# DPUNK-Schematic.net
KiCad netlist of a schematic drawn in EasyEDA
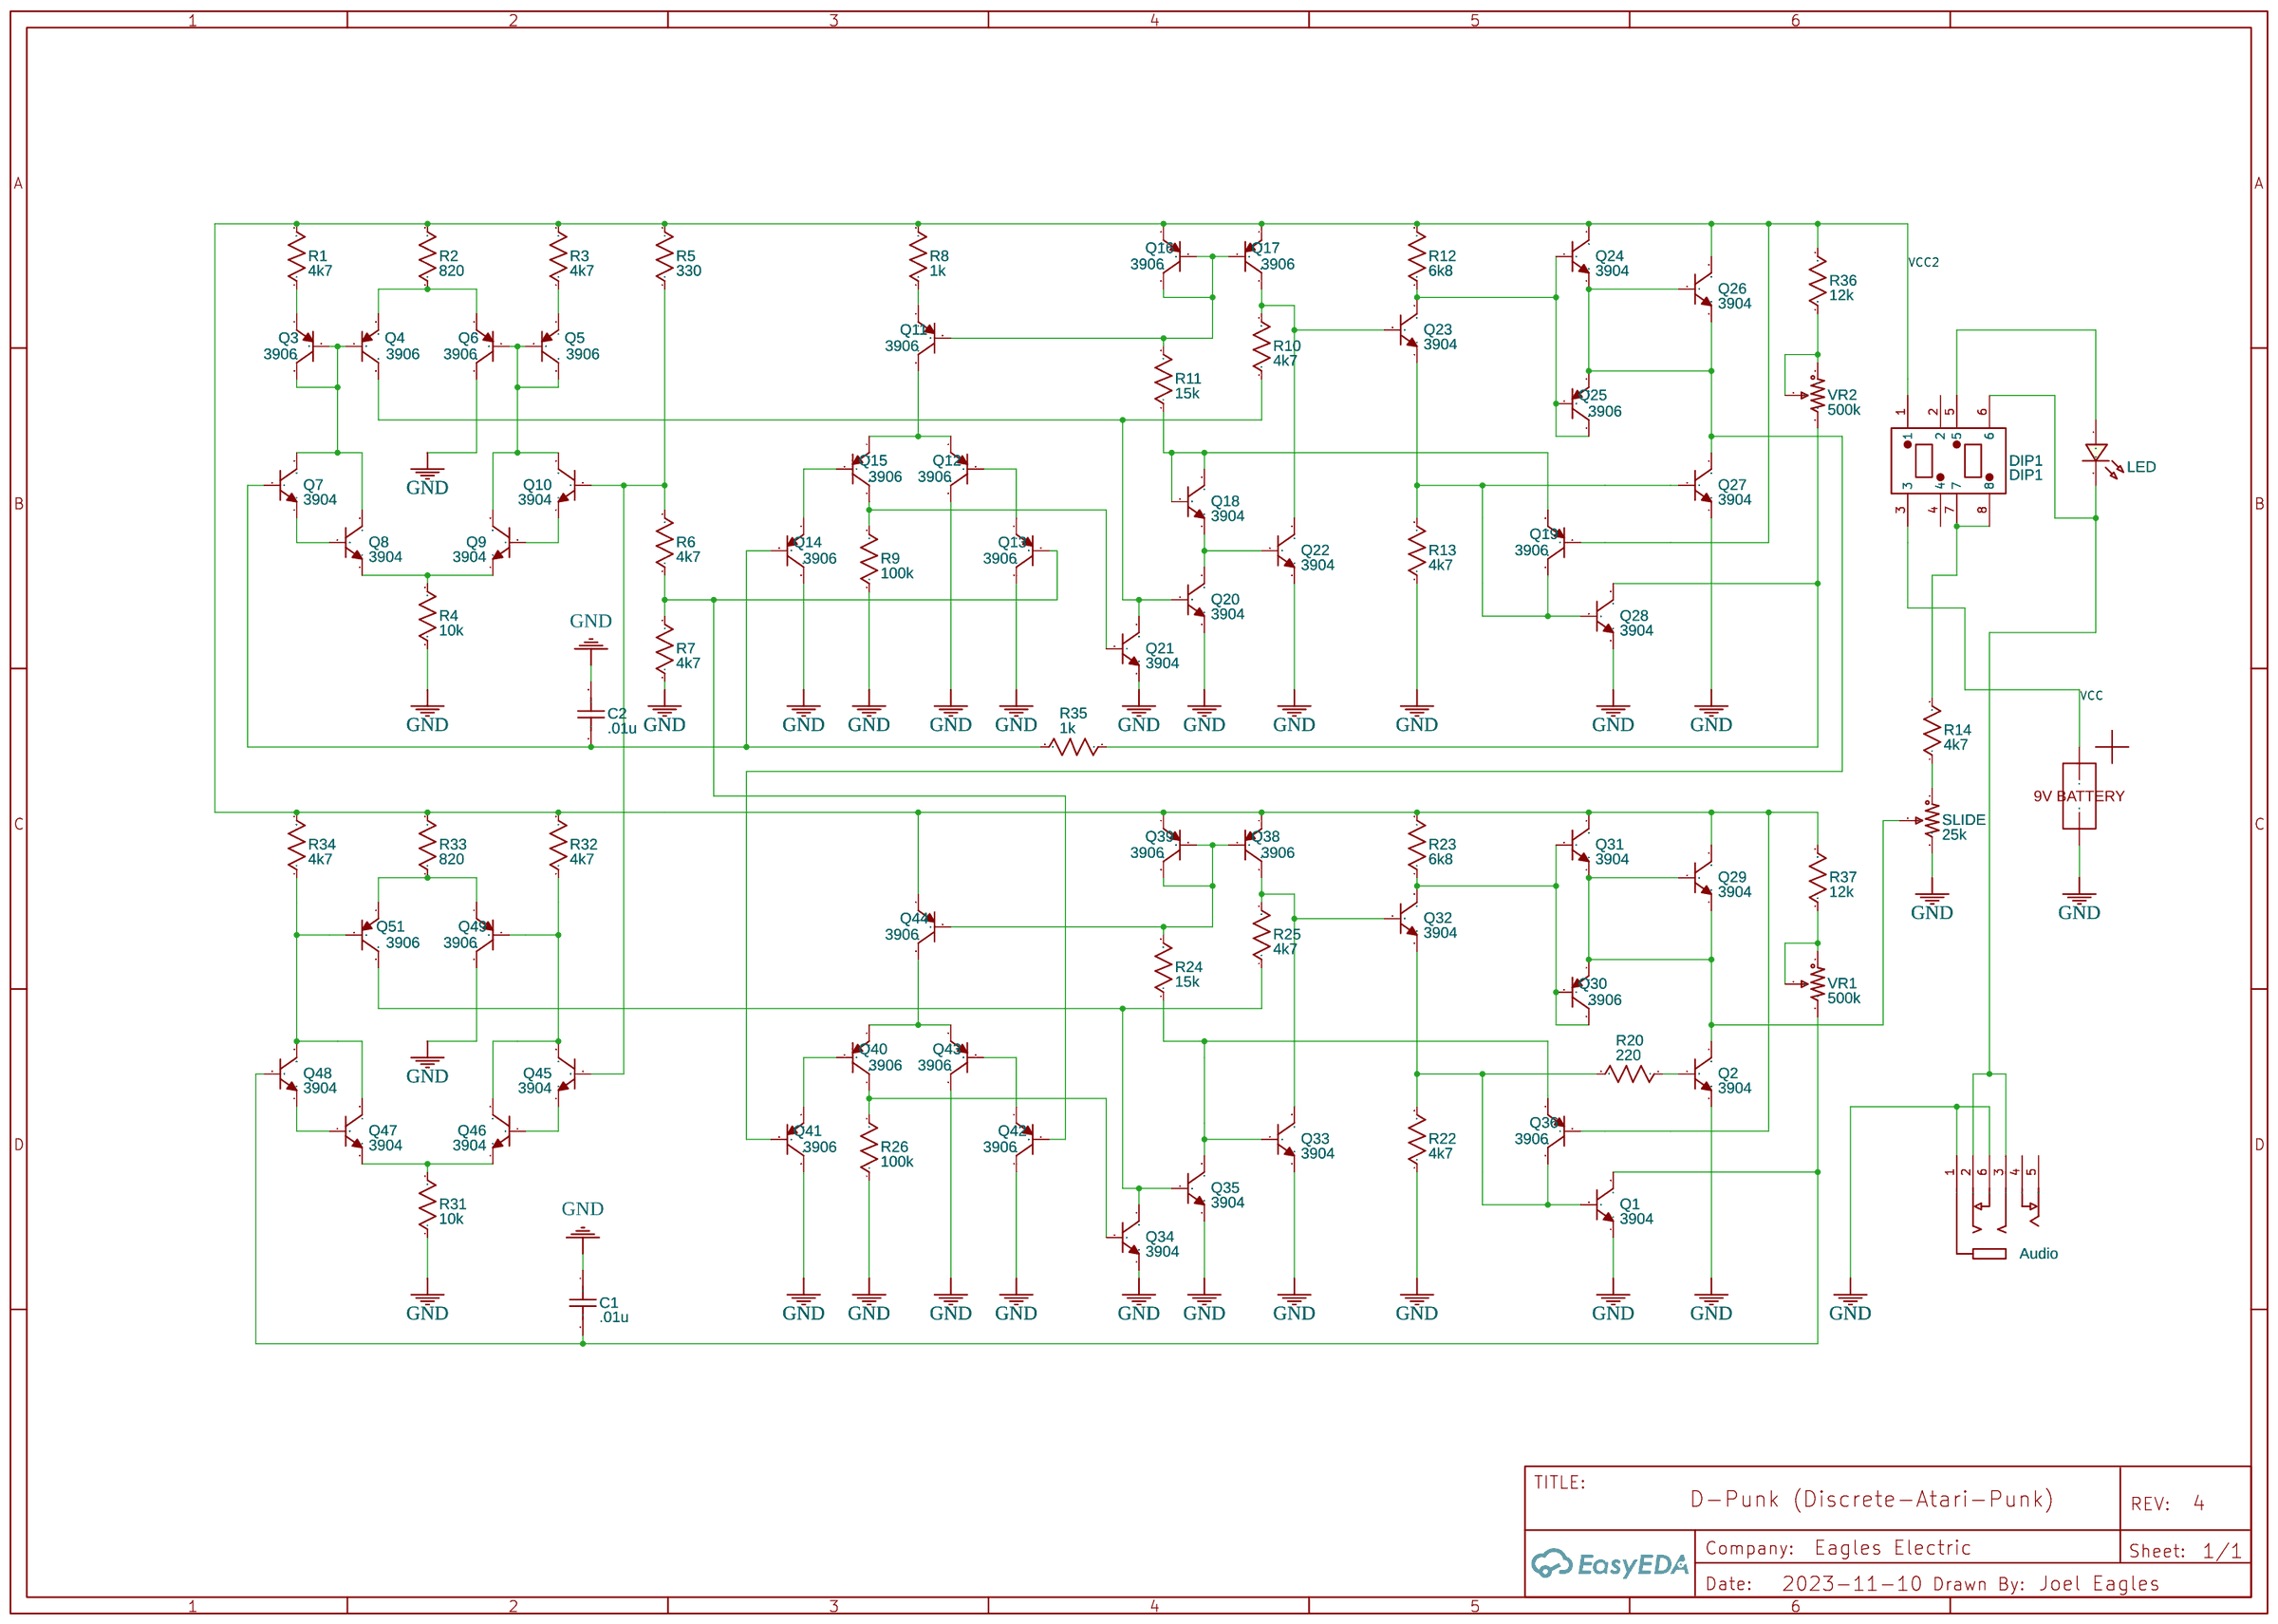
[diagram p0: schematic sheet]

(export (version "E")
  (design (tool "Eeschema 10.0.6"))
  (components
    (comp (ref "9V") (value "9v battery connector") (libsource (lib "") (part "9v battery connector")))
    (comp (ref "AUX")
      (value "Audio")
      (fields (field (name "Manufacturer") "ADAM TECH"))
      (libsource (lib "") (part "ASJ-99H-R-HT-T/R"))
    )
    (comp (ref "C1") (value ".01u") (libsource (lib "") (part "C_0603_US")))
    (comp (ref "C2") (value ".01u") (libsource (lib "") (part "C_0603_US_1")))
    (comp (ref "DIP1")
      (value "DIP1")
      (fields (field (name "Manufacturer Part") "78J02T") (field (name "Manufacturer") "Grayhill"))
      (libsource (lib "") (part "78J02T"))
    )
    (comp (ref "LED")
      (value "LED")
      (fields
        (field (name "Manufacturer Part") "333-2SURD/S530-A3")
        (field (name "Manufacturer") "EVERLIGHT(台湾亿光)")
      )
      (libsource (lib "") (part "LED-TH-5mm_R"))
    )
    (comp (ref "Q1")
      (value "3904")
      (fields (field (name "Manufacturer Part") "2N3904") (field (name "Manufacturer") "SEMTECH"))
      (libsource (lib "") (part "2N3904(TO-92)"))
    )
    (comp (ref "Q2")
      (value "3904")
      (fields (field (name "Manufacturer Part") "2N3904") (field (name "Manufacturer") "SEMTECH"))
      (libsource (lib "") (part "2N3904(TO-92)"))
    )
    (comp (ref "Q3")
      (value "3906")
      (fields (field (name "Manufacturer Part") "2N3906") (field (name "Manufacturer") "CJ"))
      (libsource (lib "") (part "2N3906(TO-92)_1"))
    )
    (comp (ref "Q4")
      (value "3906")
      (fields (field (name "Manufacturer Part") "2N3906") (field (name "Manufacturer") "CJ"))
      (libsource (lib "") (part "2N3906(TO-92)"))
    )
    (comp (ref "Q5")
      (value "3906")
      (fields (field (name "Manufacturer Part") "2N3906") (field (name "Manufacturer") "CJ"))
      (libsource (lib "") (part "2N3906(TO-92)"))
    )
    (comp (ref "Q6")
      (value "3906")
      (fields (field (name "Manufacturer Part") "2N3906") (field (name "Manufacturer") "CJ"))
      (libsource (lib "") (part "2N3906(TO-92)_1"))
    )
    (comp (ref "Q7")
      (value "3904")
      (fields (field (name "Manufacturer Part") "2N3904") (field (name "Manufacturer") "SEMTECH"))
      (libsource (lib "") (part "2N3904(TO-92)"))
    )
    (comp (ref "Q8")
      (value "3904")
      (fields (field (name "Manufacturer Part") "2N3904") (field (name "Manufacturer") "SEMTECH"))
      (libsource (lib "") (part "2N3904(TO-92)"))
    )
    (comp (ref "Q9")
      (value "3904")
      (fields (field (name "Manufacturer Part") "2N3904") (field (name "Manufacturer") "SEMTECH"))
      (libsource (lib "") (part "2N3904(TO-92)_1"))
    )
    (comp (ref "Q10")
      (value "3904")
      (fields (field (name "Manufacturer Part") "2N3904") (field (name "Manufacturer") "SEMTECH"))
      (libsource (lib "") (part "2N3904(TO-92)_1"))
    )
    (comp (ref "Q11")
      (value "3906")
      (fields (field (name "Manufacturer Part") "2N3906") (field (name "Manufacturer") "CJ"))
      (libsource (lib "") (part "2N3906(TO-92)_1"))
    )
    (comp (ref "Q12")
      (value "3906")
      (fields (field (name "Manufacturer Part") "2N3906") (field (name "Manufacturer") "CJ"))
      (libsource (lib "") (part "2N3906(TO-92)_1"))
    )
    (comp (ref "Q13")
      (value "3906")
      (fields (field (name "Manufacturer Part") "2N3906") (field (name "Manufacturer") "CJ"))
      (libsource (lib "") (part "2N3906(TO-92)_1"))
    )
    (comp (ref "Q14")
      (value "3906")
      (fields (field (name "Manufacturer Part") "2N3906") (field (name "Manufacturer") "CJ"))
      (libsource (lib "") (part "2N3906(TO-92)"))
    )
    (comp (ref "Q15")
      (value "3906")
      (fields (field (name "Manufacturer Part") "2N3906") (field (name "Manufacturer") "CJ"))
      (libsource (lib "") (part "2N3906(TO-92)"))
    )
    (comp (ref "Q16")
      (value "3906")
      (fields (field (name "Manufacturer Part") "2N3906") (field (name "Manufacturer") "CJ"))
      (libsource (lib "") (part "2N3906(TO-92)_1"))
    )
    (comp (ref "Q17")
      (value "3906")
      (fields (field (name "Manufacturer Part") "2N3906") (field (name "Manufacturer") "CJ"))
      (libsource (lib "") (part "2N3906(TO-92)"))
    )
    (comp (ref "Q18")
      (value "3904")
      (fields (field (name "Manufacturer Part") "2N3904") (field (name "Manufacturer") "SEMTECH"))
      (libsource (lib "") (part "2N3904(TO-92)"))
    )
    (comp (ref "Q19")
      (value "3906")
      (fields (field (name "Manufacturer Part") "2N3906") (field (name "Manufacturer") "CJ"))
      (libsource (lib "") (part "2N3906(TO-92)_1"))
    )
    (comp (ref "Q20")
      (value "3904")
      (fields (field (name "Manufacturer Part") "2N3904") (field (name "Manufacturer") "SEMTECH"))
      (libsource (lib "") (part "2N3904(TO-92)"))
    )
    (comp (ref "Q21")
      (value "3904")
      (fields (field (name "Manufacturer Part") "2N3904") (field (name "Manufacturer") "SEMTECH"))
      (libsource (lib "") (part "2N3904(TO-92)"))
    )
    (comp (ref "Q22")
      (value "3904")
      (fields (field (name "Manufacturer Part") "2N3904") (field (name "Manufacturer") "SEMTECH"))
      (libsource (lib "") (part "2N3904(TO-92)"))
    )
    (comp (ref "Q23")
      (value "3904")
      (fields (field (name "Manufacturer Part") "2N3904") (field (name "Manufacturer") "SEMTECH"))
      (libsource (lib "") (part "2N3904(TO-92)"))
    )
    (comp (ref "Q24")
      (value "3904")
      (fields (field (name "Manufacturer Part") "2N3904") (field (name "Manufacturer") "SEMTECH"))
      (libsource (lib "") (part "2N3904(TO-92)"))
    )
    (comp (ref "Q25")
      (value "3906")
      (fields (field (name "Manufacturer Part") "2N3906") (field (name "Manufacturer") "CJ"))
      (libsource (lib "") (part "2N3906(TO-92)"))
    )
    (comp (ref "Q26")
      (value "3904")
      (fields (field (name "Manufacturer Part") "2N3904") (field (name "Manufacturer") "SEMTECH"))
      (libsource (lib "") (part "2N3904(TO-92)"))
    )
    (comp (ref "Q27")
      (value "3904")
      (fields (field (name "Manufacturer Part") "2N3904") (field (name "Manufacturer") "SEMTECH"))
      (libsource (lib "") (part "2N3904(TO-92)"))
    )
    (comp (ref "Q28")
      (value "3904")
      (fields (field (name "Manufacturer Part") "2N3904") (field (name "Manufacturer") "SEMTECH"))
      (libsource (lib "") (part "2N3904(TO-92)"))
    )
    (comp (ref "Q29")
      (value "3904")
      (fields (field (name "Manufacturer Part") "2N3904") (field (name "Manufacturer") "SEMTECH"))
      (libsource (lib "") (part "2N3904(TO-92)"))
    )
    (comp (ref "Q30")
      (value "3906")
      (fields (field (name "Manufacturer Part") "2N3906") (field (name "Manufacturer") "CJ"))
      (libsource (lib "") (part "2N3906(TO-92)"))
    )
    (comp (ref "Q31")
      (value "3904")
      (fields (field (name "Manufacturer Part") "2N3904") (field (name "Manufacturer") "SEMTECH"))
      (libsource (lib "") (part "2N3904(TO-92)"))
    )
    (comp (ref "Q32")
      (value "3904")
      (fields (field (name "Manufacturer Part") "2N3904") (field (name "Manufacturer") "SEMTECH"))
      (libsource (lib "") (part "2N3904(TO-92)"))
    )
    (comp (ref "Q33")
      (value "3904")
      (fields (field (name "Manufacturer Part") "2N3904") (field (name "Manufacturer") "SEMTECH"))
      (libsource (lib "") (part "2N3904(TO-92)"))
    )
    (comp (ref "Q34")
      (value "3904")
      (fields (field (name "Manufacturer Part") "2N3904") (field (name "Manufacturer") "SEMTECH"))
      (libsource (lib "") (part "2N3904(TO-92)"))
    )
    (comp (ref "Q35")
      (value "3904")
      (fields (field (name "Manufacturer Part") "2N3904") (field (name "Manufacturer") "SEMTECH"))
      (libsource (lib "") (part "2N3904(TO-92)"))
    )
    (comp (ref "Q36")
      (value "3906")
      (fields (field (name "Manufacturer Part") "2N3906") (field (name "Manufacturer") "CJ"))
      (libsource (lib "") (part "2N3906(TO-92)_1"))
    )
    (comp (ref "Q38")
      (value "3906")
      (fields (field (name "Manufacturer Part") "2N3906") (field (name "Manufacturer") "CJ"))
      (libsource (lib "") (part "2N3906(TO-92)"))
    )
    (comp (ref "Q39")
      (value "3906")
      (fields (field (name "Manufacturer Part") "2N3906") (field (name "Manufacturer") "CJ"))
      (libsource (lib "") (part "2N3906(TO-92)_1"))
    )
    (comp (ref "Q40")
      (value "3906")
      (fields (field (name "Manufacturer Part") "2N3906") (field (name "Manufacturer") "CJ"))
      (libsource (lib "") (part "2N3906(TO-92)"))
    )
    (comp (ref "Q41")
      (value "3906")
      (fields (field (name "Manufacturer Part") "2N3906") (field (name "Manufacturer") "CJ"))
      (libsource (lib "") (part "2N3906(TO-92)"))
    )
    (comp (ref "Q42")
      (value "3906")
      (fields (field (name "Manufacturer Part") "2N3906") (field (name "Manufacturer") "CJ"))
      (libsource (lib "") (part "2N3906(TO-92)_1"))
    )
    (comp (ref "Q43")
      (value "3906")
      (fields (field (name "Manufacturer Part") "2N3906") (field (name "Manufacturer") "CJ"))
      (libsource (lib "") (part "2N3906(TO-92)_1"))
    )
    (comp (ref "Q44")
      (value "3906")
      (fields (field (name "Manufacturer Part") "2N3906") (field (name "Manufacturer") "CJ"))
      (libsource (lib "") (part "2N3906(TO-92)_1"))
    )
    (comp (ref "Q45")
      (value "3904")
      (fields (field (name "Manufacturer Part") "2N3904") (field (name "Manufacturer") "SEMTECH"))
      (libsource (lib "") (part "2N3904(TO-92)_1"))
    )
    (comp (ref "Q46")
      (value "3904")
      (fields (field (name "Manufacturer Part") "2N3904") (field (name "Manufacturer") "SEMTECH"))
      (libsource (lib "") (part "2N3904(TO-92)_1"))
    )
    (comp (ref "Q47")
      (value "3904")
      (fields (field (name "Manufacturer Part") "2N3904") (field (name "Manufacturer") "SEMTECH"))
      (libsource (lib "") (part "2N3904(TO-92)"))
    )
    (comp (ref "Q48")
      (value "3904")
      (fields (field (name "Manufacturer Part") "2N3904") (field (name "Manufacturer") "SEMTECH"))
      (libsource (lib "") (part "2N3904(TO-92)"))
    )
    (comp (ref "Q49")
      (value "3906")
      (fields (field (name "Manufacturer Part") "2N3906") (field (name "Manufacturer") "CJ"))
      (libsource (lib "") (part "2N3906(TO-92)_1"))
    )
    (comp (ref "Q51")
      (value "3906")
      (fields (field (name "Manufacturer Part") "2N3906") (field (name "Manufacturer") "CJ"))
      (libsource (lib "") (part "2N3906(TO-92)"))
    )
    (comp (ref "R1") (value "4k7") (libsource (lib "") (part "R_AXIAL-0.4_US")))
    (comp (ref "R2") (value "820") (libsource (lib "") (part "R_AXIAL-0.4_US")))
    (comp (ref "R3") (value "4k7") (libsource (lib "") (part "R_AXIAL-0.4_US")))
    (comp (ref "R4") (value "10k") (libsource (lib "") (part "R_AXIAL-0.4_US")))
    (comp (ref "R5") (value "330") (libsource (lib "") (part "R_AXIAL-0.4_US")))
    (comp (ref "R6") (value "4k7") (libsource (lib "") (part "R_AXIAL-0.4_US")))
    (comp (ref "R7") (value "4k7") (libsource (lib "") (part "R_AXIAL-0.4_US")))
    (comp (ref "R8") (value "1k") (libsource (lib "") (part "R_AXIAL-0.4_US")))
    (comp (ref "R9") (value "100k") (libsource (lib "") (part "R_AXIAL-0.4_US")))
    (comp (ref "R10") (value "4k7") (libsource (lib "") (part "R_AXIAL-0.4_US")))
    (comp (ref "R11") (value "15k") (libsource (lib "") (part "R_AXIAL-0.4_US")))
    (comp (ref "R12") (value "6k8") (libsource (lib "") (part "R_AXIAL-0.4_US")))
    (comp (ref "R13") (value "4k7") (libsource (lib "") (part "R_AXIAL-0.4_US")))
    (comp (ref "R14") (value "4k7") (libsource (lib "") (part "R_AXIAL-0.4_US")))
    (comp (ref "R20") (value "220") (libsource (lib "") (part "R_AXIAL-0.4_US_1")))
    (comp (ref "R22") (value "4k7") (libsource (lib "") (part "R_AXIAL-0.4_US")))
    (comp (ref "R23") (value "6k8") (libsource (lib "") (part "R_AXIAL-0.4_US")))
    (comp (ref "R24") (value "15k") (libsource (lib "") (part "R_AXIAL-0.4_US")))
    (comp (ref "R25") (value "4k7") (libsource (lib "") (part "R_AXIAL-0.4_US")))
    (comp (ref "R26") (value "100k") (libsource (lib "") (part "R_AXIAL-0.4_US")))
    (comp (ref "R31") (value "10k") (libsource (lib "") (part "R_AXIAL-0.4_US")))
    (comp (ref "R32") (value "4k7") (libsource (lib "") (part "R_AXIAL-0.4_US")))
    (comp (ref "R33") (value "820") (libsource (lib "") (part "R_AXIAL-0.4_US")))
    (comp (ref "R34") (value "4k7") (libsource (lib "") (part "R_AXIAL-0.4_US")))
    (comp (ref "R35") (value "1k") (libsource (lib "") (part "R_AXIAL-0.4_US_1")))
    (comp (ref "R36") (value "12k") (libsource (lib "") (part "R_AXIAL-0.4_US")))
    (comp (ref "R37") (value "12k") (libsource (lib "") (part "R_AXIAL-0.4_US")))
    (comp (ref "SLIDE") (value "25k") (libsource (lib "") (part "R_3386P_US_1")))
    (comp (ref "VR1") (value "500k") (libsource (lib "") (part "R_3386P_US")))
    (comp (ref "VR2") (value "500k") (libsource (lib "") (part "R_3386P_US")))
  )
  (nets
    (net (code "1") (name "/VCC") (class "Default")
      (node (ref "9V") (pin "1") (pinfunction "1_1") (pintype "unspecified"))
      (node (ref "DIP1") (pin "3") (pinfunction "3_3") (pintype "unspecified"))
    )
    (net (code "2") (name "/VCC2") (class "Default")
      (node (ref "DIP1") (pin "1") (pinfunction "1_1") (pintype "unspecified"))
      (node (ref "Q16") (pin "1") (pinfunction "E_1") (pintype "input"))
      (node (ref "Q17") (pin "1") (pinfunction "E_1") (pintype "input"))
      (node (ref "Q19") (pin "2") (pinfunction "B_2") (pintype "input"))
      (node (ref "Q24") (pin "3") (pinfunction "C_3") (pintype "unspecified"))
      (node (ref "Q26") (pin "3") (pinfunction "C_3") (pintype "unspecified"))
      (node (ref "Q29") (pin "3") (pinfunction "C_3") (pintype "unspecified"))
      (node (ref "Q31") (pin "3") (pinfunction "C_3") (pintype "unspecified"))
      (node (ref "Q36") (pin "2") (pinfunction "B_2") (pintype "input"))
      (node (ref "Q38") (pin "1") (pinfunction "E_1") (pintype "input"))
      (node (ref "Q39") (pin "1") (pinfunction "E_1") (pintype "input"))
      (node (ref "Q44") (pin "1") (pinfunction "E_1") (pintype "input"))
      (node (ref "R1") (pin "2") (pinfunction "2_2") (pintype "unspecified"))
      (node (ref "R12") (pin "2") (pinfunction "2_2") (pintype "unspecified"))
      (node (ref "R2") (pin "2") (pinfunction "2_2") (pintype "unspecified"))
      (node (ref "R23") (pin "2") (pinfunction "2_2") (pintype "unspecified"))
      (node (ref "R3") (pin "2") (pinfunction "2_2") (pintype "unspecified"))
      (node (ref "R32") (pin "2") (pinfunction "2_2") (pintype "unspecified"))
      (node (ref "R33") (pin "2") (pinfunction "2_2") (pintype "unspecified"))
      (node (ref "R34") (pin "2") (pinfunction "2_2") (pintype "unspecified"))
      (node (ref "R36") (pin "2") (pinfunction "2_2") (pintype "unspecified"))
      (node (ref "R37") (pin "2") (pinfunction "2_2") (pintype "unspecified"))
      (node (ref "R5") (pin "2") (pinfunction "2_2") (pintype "unspecified"))
      (node (ref "R8") (pin "2") (pinfunction "2_2") (pintype "unspecified"))
    )
    (net (code "3") (name "GND") (class "Default")
      (node (ref "9V") (pin "2") (pinfunction "2_2") (pintype "unspecified"))
      (node (ref "AUX") (pin "1") (pinfunction "2_1") (pintype "unspecified"))
      (node (ref "AUX") (pin "6") (pinfunction "7_6") (pintype "unspecified"))
      (node (ref "C1") (pin "1") (pinfunction "1_1") (pintype "unspecified"))
      (node (ref "C2") (pin "2") (pinfunction "2_2") (pintype "unspecified"))
      (node (ref "Q1") (pin "1") (pinfunction "E_1") (pintype "unspecified"))
      (node (ref "Q12") (pin "3") (pinfunction "C_3") (pintype "input"))
      (node (ref "Q13") (pin "3") (pinfunction "C_3") (pintype "input"))
      (node (ref "Q14") (pin "3") (pinfunction "C_3") (pintype "input"))
      (node (ref "Q2") (pin "1") (pinfunction "E_1") (pintype "unspecified"))
      (node (ref "Q20") (pin "1") (pinfunction "E_1") (pintype "unspecified"))
      (node (ref "Q21") (pin "1") (pinfunction "E_1") (pintype "unspecified"))
      (node (ref "Q22") (pin "1") (pinfunction "E_1") (pintype "unspecified"))
      (node (ref "Q27") (pin "1") (pinfunction "E_1") (pintype "unspecified"))
      (node (ref "Q28") (pin "1") (pinfunction "E_1") (pintype "unspecified"))
      (node (ref "Q33") (pin "1") (pinfunction "E_1") (pintype "unspecified"))
      (node (ref "Q34") (pin "1") (pinfunction "E_1") (pintype "unspecified"))
      (node (ref "Q35") (pin "1") (pinfunction "E_1") (pintype "unspecified"))
      (node (ref "Q41") (pin "3") (pinfunction "C_3") (pintype "input"))
      (node (ref "Q42") (pin "3") (pinfunction "C_3") (pintype "input"))
      (node (ref "Q43") (pin "3") (pinfunction "C_3") (pintype "input"))
      (node (ref "Q49") (pin "3") (pinfunction "C_3") (pintype "input"))
      (node (ref "Q6") (pin "3") (pinfunction "C_3") (pintype "input"))
      (node (ref "R13") (pin "1") (pinfunction "1_1") (pintype "unspecified"))
      (node (ref "R22") (pin "1") (pinfunction "1_1") (pintype "unspecified"))
      (node (ref "R26") (pin "1") (pinfunction "1_1") (pintype "unspecified"))
      (node (ref "R31") (pin "1") (pinfunction "1_1") (pintype "unspecified"))
      (node (ref "R4") (pin "1") (pinfunction "1_1") (pintype "unspecified"))
      (node (ref "R7") (pin "1") (pinfunction "1_1") (pintype "unspecified"))
      (node (ref "R9") (pin "1") (pinfunction "1_1") (pintype "unspecified"))
      (node (ref "SLIDE") (pin "3") (pinfunction "3_3") (pintype "unspecified"))
    )
    (net (code "4") (name "Net-(AUX-3)") (class "Default")
      (node (ref "AUX") (pin "2") (pinfunction "3_2") (pintype "unspecified"))
      (node (ref "AUX") (pin "3") (pinfunction "4_3") (pintype "unspecified"))
      (node (ref "DIP1") (pin "6") (pinfunction "6_6") (pintype "unspecified"))
      (node (ref "LED") (pin "2") (pinfunction "2_2") (pintype "unspecified"))
    )
    (net (code "5") (name "Net-(DIP1-Pad5)") (class "Default")
      (node (ref "DIP1") (pin "5") (pinfunction "5_5") (pintype "unspecified"))
      (node (ref "LED") (pin "1") (pinfunction "1_1") (pintype "unspecified"))
    )
    (net (code "6") (name "Net-(DIP1-Pad7)") (class "Default")
      (node (ref "DIP1") (pin "7") (pinfunction "7_7") (pintype "unspecified"))
      (node (ref "DIP1") (pin "8") (pinfunction "8_8") (pintype "unspecified"))
      (node (ref "R14") (pin "2") (pinfunction "2_2") (pintype "unspecified"))
    )
    (net (code "7") (name "Net-(Q1-B)") (class "Default")
      (node (ref "Q1") (pin "2") (pinfunction "B_2") (pintype "unspecified"))
      (node (ref "Q32") (pin "1") (pinfunction "E_1") (pintype "unspecified"))
      (node (ref "Q36") (pin "3") (pinfunction "C_3") (pintype "input"))
      (node (ref "R20") (pin "2") (pinfunction "2_2") (pintype "unspecified"))
      (node (ref "R22") (pin "2") (pinfunction "2_2") (pintype "unspecified"))
    )
    (net (code "8") (name "Net-(Q1-C)") (class "Default")
      (node (ref "C1") (pin "2") (pinfunction "2_2") (pintype "unspecified"))
      (node (ref "Q1") (pin "3") (pinfunction "C_3") (pintype "unspecified"))
      (node (ref "Q48") (pin "2") (pinfunction "B_2") (pintype "unspecified"))
      (node (ref "VR1") (pin "3") (pinfunction "3_3") (pintype "unspecified"))
    )
    (net (code "9") (name "Net-(Q2-B)") (class "Default")
      (node (ref "Q2") (pin "2") (pinfunction "B_2") (pintype "unspecified"))
      (node (ref "R20") (pin "1") (pinfunction "1_1") (pintype "unspecified"))
    )
    (net (code "10") (name "Net-(Q2-C)") (class "Default")
      (node (ref "Q2") (pin "3") (pinfunction "C_3") (pintype "unspecified"))
      (node (ref "Q29") (pin "1") (pinfunction "E_1") (pintype "unspecified"))
      (node (ref "Q29") (pin "2") (pinfunction "B_2") (pintype "unspecified"))
      (node (ref "Q30") (pin "1") (pinfunction "E_1") (pintype "input"))
      (node (ref "Q31") (pin "1") (pinfunction "E_1") (pintype "unspecified"))
      (node (ref "SLIDE") (pin "2") (pinfunction "2_2") (pintype "unspecified"))
    )
    (net (code "11") (name "Net-(Q3-B)") (class "Default")
      (node (ref "Q3") (pin "2") (pinfunction "B_2") (pintype "input"))
      (node (ref "Q3") (pin "3") (pinfunction "C_3") (pintype "input"))
      (node (ref "Q4") (pin "2") (pinfunction "B_2") (pintype "input"))
      (node (ref "Q7") (pin "3") (pinfunction "C_3") (pintype "unspecified"))
      (node (ref "Q8") (pin "3") (pinfunction "C_3") (pintype "unspecified"))
    )
    (net (code "12") (name "Net-(Q3-E)") (class "Default")
      (node (ref "Q3") (pin "1") (pinfunction "E_1") (pintype "input"))
      (node (ref "R1") (pin "1") (pinfunction "1_1") (pintype "unspecified"))
    )
    (net (code "13") (name "Net-(Q4-E)") (class "Default")
      (node (ref "Q4") (pin "1") (pinfunction "E_1") (pintype "input"))
      (node (ref "Q6") (pin "1") (pinfunction "E_1") (pintype "input"))
      (node (ref "R2") (pin "1") (pinfunction "1_1") (pintype "unspecified"))
    )
    (net (code "14") (name "Net-(Q5-E)") (class "Default")
      (node (ref "Q5") (pin "1") (pinfunction "E_1") (pintype "input"))
      (node (ref "R3") (pin "1") (pinfunction "1_1") (pintype "unspecified"))
    )
    (net (code "15") (name "Net-(Q7-E)") (class "Default")
      (node (ref "Q7") (pin "1") (pinfunction "E_1") (pintype "unspecified"))
      (node (ref "Q8") (pin "2") (pinfunction "B_2") (pintype "unspecified"))
    )
    (net (code "16") (name "Net-(Q8-E)") (class "Default")
      (node (ref "Q8") (pin "1") (pinfunction "E_1") (pintype "unspecified"))
      (node (ref "Q9") (pin "1") (pinfunction "E_1") (pintype "unspecified"))
      (node (ref "R4") (pin "2") (pinfunction "2_2") (pintype "unspecified"))
    )
    (net (code "17") (name "Net-(Q10-B)") (class "Default")
      (node (ref "Q10") (pin "2") (pinfunction "B_2") (pintype "unspecified"))
      (node (ref "Q45") (pin "2") (pinfunction "B_2") (pintype "unspecified"))
      (node (ref "R5") (pin "1") (pinfunction "1_1") (pintype "unspecified"))
      (node (ref "R6") (pin "2") (pinfunction "2_2") (pintype "unspecified"))
    )
    (net (code "18") (name "Net-(Q10-C)") (class "Default")
      (node (ref "Q10") (pin "3") (pinfunction "C_3") (pintype "unspecified"))
      (node (ref "Q5") (pin "2") (pinfunction "B_2") (pintype "input"))
      (node (ref "Q5") (pin "3") (pinfunction "C_3") (pintype "input"))
      (node (ref "Q6") (pin "2") (pinfunction "B_2") (pintype "input"))
      (node (ref "Q9") (pin "3") (pinfunction "C_3") (pintype "unspecified"))
    )
    (net (code "19") (name "Net-(Q10-E)") (class "Default")
      (node (ref "Q10") (pin "1") (pinfunction "E_1") (pintype "unspecified"))
      (node (ref "Q9") (pin "2") (pinfunction "B_2") (pintype "unspecified"))
    )
    (net (code "20") (name "Net-(Q11-B)") (class "Default")
      (node (ref "Q11") (pin "2") (pinfunction "B_2") (pintype "input"))
      (node (ref "Q16") (pin "2") (pinfunction "B_2") (pintype "input"))
      (node (ref "Q16") (pin "3") (pinfunction "C_3") (pintype "input"))
      (node (ref "Q17") (pin "2") (pinfunction "B_2") (pintype "input"))
      (node (ref "R11") (pin "2") (pinfunction "2_2") (pintype "unspecified"))
    )
    (net (code "21") (name "Net-(Q11-C)") (class "Default")
      (node (ref "Q11") (pin "3") (pinfunction "C_3") (pintype "input"))
      (node (ref "Q12") (pin "1") (pinfunction "E_1") (pintype "input"))
      (node (ref "Q15") (pin "1") (pinfunction "E_1") (pintype "input"))
    )
    (net (code "22") (name "Net-(Q11-E)") (class "Default")
      (node (ref "Q11") (pin "1") (pinfunction "E_1") (pintype "input"))
      (node (ref "R8") (pin "1") (pinfunction "1_1") (pintype "unspecified"))
    )
    (net (code "23") (name "Net-(Q12-B)") (class "Default")
      (node (ref "Q12") (pin "2") (pinfunction "B_2") (pintype "input"))
      (node (ref "Q13") (pin "1") (pinfunction "E_1") (pintype "input"))
    )
    (net (code "24") (name "Net-(Q13-B)") (class "Default")
      (node (ref "Q13") (pin "2") (pinfunction "B_2") (pintype "input"))
      (node (ref "Q42") (pin "2") (pinfunction "B_2") (pintype "input"))
      (node (ref "R6") (pin "1") (pinfunction "1_1") (pintype "unspecified"))
      (node (ref "R7") (pin "2") (pinfunction "2_2") (pintype "unspecified"))
    )
    (net (code "25") (name "Net-(Q14-B)") (class "Default")
      (node (ref "C2") (pin "1") (pinfunction "1_1") (pintype "unspecified"))
      (node (ref "Q14") (pin "2") (pinfunction "B_2") (pintype "input"))
      (node (ref "Q7") (pin "2") (pinfunction "B_2") (pintype "unspecified"))
      (node (ref "R35") (pin "2") (pinfunction "2_2") (pintype "unspecified"))
    )
    (net (code "26") (name "Net-(Q14-E)") (class "Default")
      (node (ref "Q14") (pin "1") (pinfunction "E_1") (pintype "input"))
      (node (ref "Q15") (pin "2") (pinfunction "B_2") (pintype "input"))
    )
    (net (code "27") (name "Net-(Q15-C)") (class "Default")
      (node (ref "Q15") (pin "3") (pinfunction "C_3") (pintype "input"))
      (node (ref "Q21") (pin "2") (pinfunction "B_2") (pintype "unspecified"))
      (node (ref "R9") (pin "2") (pinfunction "2_2") (pintype "unspecified"))
    )
    (net (code "28") (name "Net-(Q17-C)") (class "Default")
      (node (ref "Q17") (pin "3") (pinfunction "C_3") (pintype "input"))
      (node (ref "Q22") (pin "3") (pinfunction "C_3") (pintype "unspecified"))
      (node (ref "Q23") (pin "2") (pinfunction "B_2") (pintype "unspecified"))
      (node (ref "R10") (pin "2") (pinfunction "2_2") (pintype "unspecified"))
    )
    (net (code "29") (name "Net-(Q18-B)") (class "Default")
      (node (ref "Q18") (pin "2") (pinfunction "B_2") (pintype "unspecified"))
      (node (ref "Q18") (pin "3") (pinfunction "C_3") (pintype "unspecified"))
      (node (ref "Q19") (pin "1") (pinfunction "E_1") (pintype "input"))
      (node (ref "R11") (pin "1") (pinfunction "1_1") (pintype "unspecified"))
    )
    (net (code "30") (name "Net-(Q18-E)") (class "Default")
      (node (ref "Q18") (pin "1") (pinfunction "E_1") (pintype "unspecified"))
      (node (ref "Q20") (pin "3") (pinfunction "C_3") (pintype "unspecified"))
      (node (ref "Q22") (pin "2") (pinfunction "B_2") (pintype "unspecified"))
    )
    (net (code "31") (name "Net-(Q19-C)") (class "Default")
      (node (ref "Q19") (pin "3") (pinfunction "C_3") (pintype "input"))
      (node (ref "Q23") (pin "1") (pinfunction "E_1") (pintype "unspecified"))
      (node (ref "Q27") (pin "2") (pinfunction "B_2") (pintype "unspecified"))
      (node (ref "Q28") (pin "2") (pinfunction "B_2") (pintype "unspecified"))
      (node (ref "R13") (pin "2") (pinfunction "2_2") (pintype "unspecified"))
    )
    (net (code "32") (name "Net-(Q20-B)") (class "Default")
      (node (ref "Q20") (pin "2") (pinfunction "B_2") (pintype "unspecified"))
      (node (ref "Q21") (pin "3") (pinfunction "C_3") (pintype "unspecified"))
      (node (ref "Q4") (pin "3") (pinfunction "C_3") (pintype "input"))
      (node (ref "R10") (pin "1") (pinfunction "1_1") (pintype "unspecified"))
    )
    (net (code "33") (name "Net-(Q23-C)") (class "Default")
      (node (ref "Q23") (pin "3") (pinfunction "C_3") (pintype "unspecified"))
      (node (ref "Q24") (pin "2") (pinfunction "B_2") (pintype "unspecified"))
      (node (ref "Q25") (pin "2") (pinfunction "B_2") (pintype "input"))
      (node (ref "Q25") (pin "3") (pinfunction "C_3") (pintype "input"))
      (node (ref "R12") (pin "1") (pinfunction "1_1") (pintype "unspecified"))
    )
    (net (code "34") (name "Net-(Q24-E)") (class "Default")
      (node (ref "Q24") (pin "1") (pinfunction "E_1") (pintype "unspecified"))
      (node (ref "Q25") (pin "1") (pinfunction "E_1") (pintype "input"))
      (node (ref "Q26") (pin "1") (pinfunction "E_1") (pintype "unspecified"))
      (node (ref "Q26") (pin "2") (pinfunction "B_2") (pintype "unspecified"))
      (node (ref "Q27") (pin "3") (pinfunction "C_3") (pintype "unspecified"))
      (node (ref "Q41") (pin "2") (pinfunction "B_2") (pintype "input"))
    )
    (net (code "35") (name "Net-(Q28-C)") (class "Default")
      (node (ref "Q28") (pin "3") (pinfunction "C_3") (pintype "unspecified"))
      (node (ref "R35") (pin "1") (pinfunction "1_1") (pintype "unspecified"))
      (node (ref "VR2") (pin "3") (pinfunction "3_3") (pintype "unspecified"))
    )
    (net (code "36") (name "Net-(Q30-B)") (class "Default")
      (node (ref "Q30") (pin "2") (pinfunction "B_2") (pintype "input"))
      (node (ref "Q30") (pin "3") (pinfunction "C_3") (pintype "input"))
      (node (ref "Q31") (pin "2") (pinfunction "B_2") (pintype "unspecified"))
      (node (ref "Q32") (pin "3") (pinfunction "C_3") (pintype "unspecified"))
      (node (ref "R23") (pin "1") (pinfunction "1_1") (pintype "unspecified"))
    )
    (net (code "37") (name "Net-(Q32-B)") (class "Default")
      (node (ref "Q32") (pin "2") (pinfunction "B_2") (pintype "unspecified"))
      (node (ref "Q33") (pin "3") (pinfunction "C_3") (pintype "unspecified"))
      (node (ref "Q38") (pin "3") (pinfunction "C_3") (pintype "input"))
      (node (ref "R25") (pin "2") (pinfunction "2_2") (pintype "unspecified"))
    )
    (net (code "38") (name "Net-(Q33-B)") (class "Default")
      (node (ref "Q33") (pin "2") (pinfunction "B_2") (pintype "unspecified"))
      (node (ref "Q35") (pin "3") (pinfunction "C_3") (pintype "unspecified"))
      (node (ref "Q36") (pin "1") (pinfunction "E_1") (pintype "input"))
      (node (ref "R24") (pin "1") (pinfunction "1_1") (pintype "unspecified"))
    )
    (net (code "39") (name "Net-(Q34-B)") (class "Default")
      (node (ref "Q34") (pin "2") (pinfunction "B_2") (pintype "unspecified"))
      (node (ref "Q40") (pin "3") (pinfunction "C_3") (pintype "input"))
      (node (ref "R26") (pin "2") (pinfunction "2_2") (pintype "unspecified"))
    )
    (net (code "40") (name "Net-(Q34-C)") (class "Default")
      (node (ref "Q34") (pin "3") (pinfunction "C_3") (pintype "unspecified"))
      (node (ref "Q35") (pin "2") (pinfunction "B_2") (pintype "unspecified"))
      (node (ref "Q51") (pin "3") (pinfunction "C_3") (pintype "input"))
      (node (ref "R25") (pin "1") (pinfunction "1_1") (pintype "unspecified"))
    )
    (net (code "41") (name "Net-(Q38-B)") (class "Default")
      (node (ref "Q38") (pin "2") (pinfunction "B_2") (pintype "input"))
      (node (ref "Q39") (pin "2") (pinfunction "B_2") (pintype "input"))
      (node (ref "Q39") (pin "3") (pinfunction "C_3") (pintype "input"))
      (node (ref "Q44") (pin "2") (pinfunction "B_2") (pintype "input"))
      (node (ref "R24") (pin "2") (pinfunction "2_2") (pintype "unspecified"))
    )
    (net (code "42") (name "Net-(Q40-B)") (class "Default")
      (node (ref "Q40") (pin "2") (pinfunction "B_2") (pintype "input"))
      (node (ref "Q41") (pin "1") (pinfunction "E_1") (pintype "input"))
    )
    (net (code "43") (name "Net-(Q40-E)") (class "Default")
      (node (ref "Q40") (pin "1") (pinfunction "E_1") (pintype "input"))
      (node (ref "Q43") (pin "1") (pinfunction "E_1") (pintype "input"))
      (node (ref "Q44") (pin "3") (pinfunction "C_3") (pintype "input"))
    )
    (net (code "44") (name "Net-(Q42-E)") (class "Default")
      (node (ref "Q42") (pin "1") (pinfunction "E_1") (pintype "input"))
      (node (ref "Q43") (pin "2") (pinfunction "B_2") (pintype "input"))
    )
    (net (code "45") (name "Net-(Q45-C)") (class "Default")
      (node (ref "Q45") (pin "3") (pinfunction "C_3") (pintype "unspecified"))
      (node (ref "Q46") (pin "3") (pinfunction "C_3") (pintype "unspecified"))
      (node (ref "Q49") (pin "2") (pinfunction "B_2") (pintype "input"))
      (node (ref "R32") (pin "1") (pinfunction "1_1") (pintype "unspecified"))
    )
    (net (code "46") (name "Net-(Q45-E)") (class "Default")
      (node (ref "Q45") (pin "1") (pinfunction "E_1") (pintype "unspecified"))
      (node (ref "Q46") (pin "2") (pinfunction "B_2") (pintype "unspecified"))
    )
    (net (code "47") (name "Net-(Q46-E)") (class "Default")
      (node (ref "Q46") (pin "1") (pinfunction "E_1") (pintype "unspecified"))
      (node (ref "Q47") (pin "1") (pinfunction "E_1") (pintype "unspecified"))
      (node (ref "R31") (pin "2") (pinfunction "2_2") (pintype "unspecified"))
    )
    (net (code "48") (name "Net-(Q47-B)") (class "Default")
      (node (ref "Q47") (pin "2") (pinfunction "B_2") (pintype "unspecified"))
      (node (ref "Q48") (pin "1") (pinfunction "E_1") (pintype "unspecified"))
    )
    (net (code "49") (name "Net-(Q47-C)") (class "Default")
      (node (ref "Q47") (pin "3") (pinfunction "C_3") (pintype "unspecified"))
      (node (ref "Q48") (pin "3") (pinfunction "C_3") (pintype "unspecified"))
      (node (ref "Q51") (pin "2") (pinfunction "B_2") (pintype "input"))
      (node (ref "R34") (pin "1") (pinfunction "1_1") (pintype "unspecified"))
    )
    (net (code "50") (name "Net-(Q49-E)") (class "Default")
      (node (ref "Q49") (pin "1") (pinfunction "E_1") (pintype "input"))
      (node (ref "Q51") (pin "1") (pinfunction "E_1") (pintype "input"))
      (node (ref "R33") (pin "1") (pinfunction "1_1") (pintype "unspecified"))
    )
    (net (code "51") (name "Net-(R14-Pad1)") (class "Default")
      (node (ref "R14") (pin "1") (pinfunction "1_1") (pintype "unspecified"))
      (node (ref "SLIDE") (pin "1") (pinfunction "1_1") (pintype "unspecified"))
    )
    (net (code "52") (name "Net-(R36-Pad1)") (class "Default")
      (node (ref "R36") (pin "1") (pinfunction "1_1") (pintype "unspecified"))
      (node (ref "VR2") (pin "1") (pinfunction "1_1") (pintype "unspecified"))
      (node (ref "VR2") (pin "2") (pinfunction "2_2") (pintype "unspecified"))
    )
    (net (code "53") (name "Net-(R37-Pad1)") (class "Default")
      (node (ref "R37") (pin "1") (pinfunction "1_1") (pintype "unspecified"))
      (node (ref "VR1") (pin "1") (pinfunction "1_1") (pintype "unspecified"))
      (node (ref "VR1") (pin "2") (pinfunction "2_2") (pintype "unspecified"))
    )
    (net (code "54") (name "unconnected-(AUX-5-Pad4)") (class "Default")
      (node (ref "AUX") (pin "4") (pinfunction "5_4") (pintype "unspecified"))
    )
    (net (code "55") (name "unconnected-(AUX-6-Pad5)") (class "Default")
      (node (ref "AUX") (pin "5") (pinfunction "6_5") (pintype "unspecified"))
    )
    (net (code "56") (name "unconnected-(DIP1-Pad2)") (class "Default")
      (node (ref "DIP1") (pin "2") (pinfunction "2_2") (pintype "unspecified"))
    )
    (net (code "57") (name "unconnected-(DIP1-Pad4)") (class "Default")
      (node (ref "DIP1") (pin "4") (pinfunction "4_4") (pintype "unspecified"))
    )
  )
)
